# Sheet2.net
KiCad netlist of a schematic drawn in Altium Designer
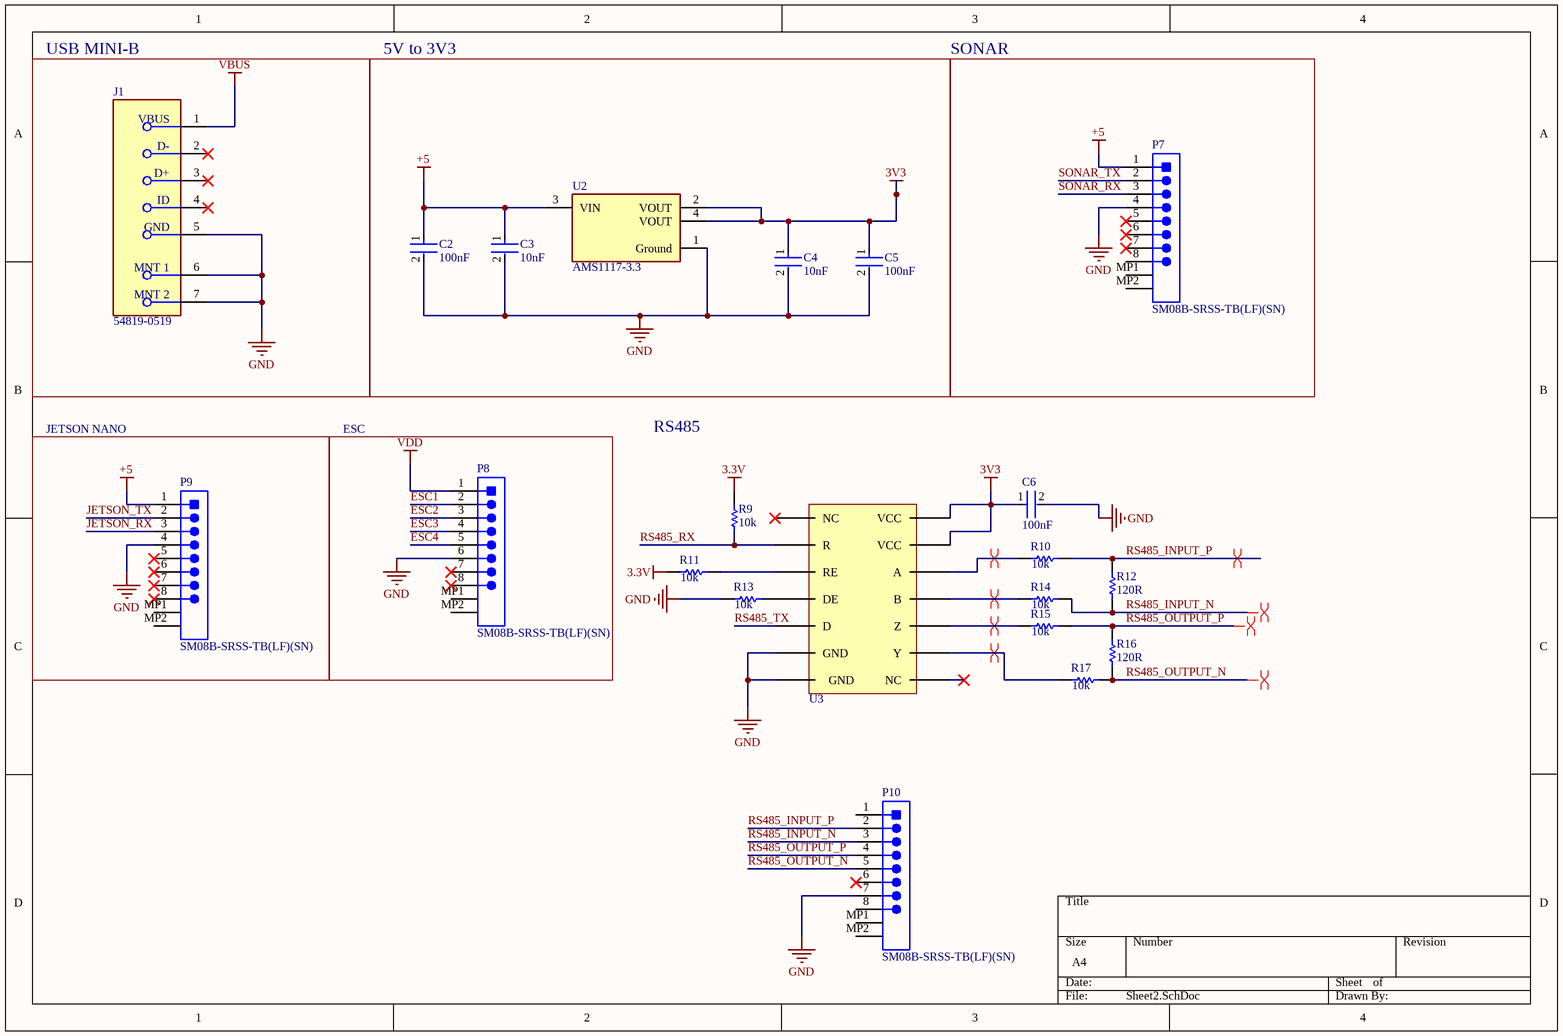
[diagram p0: Sheet2.SchDoc]

(export (version "E")
  (design (tool "Eeschema 10.0.6"))
  (components
    (comp (ref "C2")
      (value "100nF")
      (footprint "FP-C0402-BB-MFG")
      (description "CAP CER 0.1UF 10V X5R 0402")
      (fields (field (name "MANUFACTURER") "Kemet") (field (name "TOLERANCE") "0.1"))
      (libsource (lib "Altium Content Vault") (part "b4654b650e69147ec39a6b967a45e02"))
    )
    (comp (ref "C3")
      (value "10nF")
      (footprint "FP-C0402-BB-MFG")
      (description "CAP CER 0.1UF 10V X5R 0402")
      (fields (field (name "MANUFACTURER") "Kemet") (field (name "TOLERANCE") "0.1"))
      (libsource (lib "Altium Content Vault") (part "b4654b650e69147ec39a6b967a45e02"))
    )
    (comp (ref "C4")
      (value "10nF")
      (footprint "FP-C0402-BB-MFG")
      (description "CAP CER 0.1UF 10V X5R 0402")
      (fields (field (name "MANUFACTURER") "Kemet") (field (name "TOLERANCE") "0.1"))
      (libsource (lib "Altium Content Vault") (part "b4654b650e69147ec39a6b967a45e02"))
    )
    (comp (ref "C5")
      (value "100nF")
      (footprint "FP-C0402-BB-MFG")
      (description "CAP CER 0.1UF 10V X5R 0402")
      (fields (field (name "MANUFACTURER") "Kemet") (field (name "TOLERANCE") "0.1"))
      (libsource (lib "Altium Content Vault") (part "b4654b650e69147ec39a6b967a45e02"))
    )
    (comp (ref "C6")
      (value "100nF")
      (footprint "FP-C0402-BB-MFG")
      (description "CAP CER 0.1UF 10V X5R 0402")
      (fields (field (name "MANUFACTURER") "Kemet") (field (name "TOLERANCE") "0.1"))
      (libsource (lib "Altium Content Vault") (part "b4654b650e69147ec39a6b967a45e02"))
    )
    (comp (ref "J1")
      (value "54819-0519")
      (footprint "FP-54819-0519-MFG")
      (description "CONN RCPT USB2.0 MINI B 5P R/A")
      (libsource (lib "Altium Content Vault") (part "0bee2869d159fa7a73e2a5ef735a9a6"))
    )
    (comp (ref "P7")
      (value "SM08B-SRSS-TB(LF)(SN)")
      (footprint "JST-SM08B-SRSS-TB_V")
      (description "Male Header, Pitch 1 mm, 1 x 8 Position, Height 2.95 mm, -25 to 85 degC, RoHS, Tape and Reel")
      (fields (field (name "MANUFACTURER") "JST"))
      (libsource (lib "Altium Content Vault") (part "CN-1P-2M-R8"))
    )
    (comp (ref "P8")
      (value "SM08B-SRSS-TB(LF)(SN)")
      (footprint "JST-SM08B-SRSS-TB_V")
      (description "Male Header, Pitch 1 mm, 1 x 8 Position, Height 2.95 mm, -25 to 85 degC, RoHS, Tape and Reel")
      (fields (field (name "MANUFACTURER") "JST"))
      (libsource (lib "Altium Content Vault") (part "CN-1P-2M-R8"))
    )
    (comp (ref "P9")
      (value "SM08B-SRSS-TB(LF)(SN)")
      (footprint "JST-SM08B-SRSS-TB_V")
      (description "Male Header, Pitch 1 mm, 1 x 8 Position, Height 2.95 mm, -25 to 85 degC, RoHS, Tape and Reel")
      (fields (field (name "MANUFACTURER") "JST"))
      (libsource (lib "Altium Content Vault") (part "CN-1P-2M-R8"))
    )
    (comp (ref "P10")
      (value "SM08B-SRSS-TB(LF)(SN)")
      (footprint "JST-SM08B-SRSS-TB_V")
      (description "Male Header, Pitch 1 mm, 1 x 8 Position, Height 2.95 mm, -25 to 85 degC, RoHS, Tape and Reel")
      (fields (field (name "MANUFACTURER") "JST"))
      (libsource (lib "Altium Content Vault") (part "CN-1P-2M-R8"))
    )
    (comp (ref "R9")
      (value "10k")
      (footprint "RESC1609X50X30LL8T20")
      (description "Chip Resistor, 10 KOhm, +/- 1%, 100 mW, -55 to 155 degC, 0603 (1608 Metric), RoHS, Tape and Reel")
      (fields (field (name "MANUFACTURER") "Vishay Semiconductor"))
      (libsource (lib "Altium Content Vault") (part "RES-2"))
    )
    (comp (ref "R10")
      (value "10k")
      (footprint "RESC1609X50X30LL8T20")
      (description "Chip Resistor, 10 KOhm, +/- 1%, 100 mW, -55 to 155 degC, 0603 (1608 Metric), RoHS, Tape and Reel")
      (fields (field (name "MANUFACTURER") "Vishay Semiconductor"))
      (libsource (lib "Altium Content Vault") (part "RES-2"))
    )
    (comp (ref "R11")
      (value "10k")
      (footprint "RESC1609X50X30LL8T20")
      (description "Chip Resistor, 10 KOhm, +/- 1%, 100 mW, -55 to 155 degC, 0603 (1608 Metric), RoHS, Tape and Reel")
      (fields (field (name "MANUFACTURER") "Vishay Semiconductor"))
      (libsource (lib "Altium Content Vault") (part "RES-2"))
    )
    (comp (ref "R12")
      (value "120R")
      (footprint "RESC1609X50X30LL8T20")
      (description "Chip Resistor, 10 KOhm, +/- 1%, 100 mW, -55 to 155 degC, 0603 (1608 Metric), RoHS, Tape and Reel")
      (fields (field (name "MANUFACTURER") "Vishay Semiconductor"))
      (libsource (lib "Altium Content Vault") (part "RES-2"))
    )
    (comp (ref "R13")
      (value "10k")
      (footprint "RESC1609X50X30LL8T20")
      (description "Chip Resistor, 10 KOhm, +/- 1%, 100 mW, -55 to 155 degC, 0603 (1608 Metric), RoHS, Tape and Reel")
      (fields (field (name "MANUFACTURER") "Vishay Semiconductor"))
      (libsource (lib "Altium Content Vault") (part "RES-2"))
    )
    (comp (ref "R14")
      (value "10k")
      (footprint "RESC1609X50X30LL8T20")
      (description "Chip Resistor, 10 KOhm, +/- 1%, 100 mW, -55 to 155 degC, 0603 (1608 Metric), RoHS, Tape and Reel")
      (fields (field (name "MANUFACTURER") "Vishay Semiconductor"))
      (libsource (lib "Altium Content Vault") (part "RES-2"))
    )
    (comp (ref "R15")
      (value "10k")
      (footprint "RESC1609X50X30LL8T20")
      (description "Chip Resistor, 10 KOhm, +/- 1%, 100 mW, -55 to 155 degC, 0603 (1608 Metric), RoHS, Tape and Reel")
      (fields (field (name "MANUFACTURER") "Vishay Semiconductor"))
      (libsource (lib "Altium Content Vault") (part "RES-2"))
    )
    (comp (ref "R16")
      (value "120R")
      (footprint "RESC1609X50X30LL8T20")
      (description "Chip Resistor, 10 KOhm, +/- 1%, 100 mW, -55 to 155 degC, 0603 (1608 Metric), RoHS, Tape and Reel")
      (fields (field (name "MANUFACTURER") "Vishay Semiconductor"))
      (libsource (lib "Altium Content Vault") (part "RES-2"))
    )
    (comp (ref "R17")
      (value "10k")
      (footprint "RESC1609X50X30LL8T20")
      (description "Chip Resistor, 10 KOhm, +/- 1%, 100 mW, -55 to 155 degC, 0603 (1608 Metric), RoHS, Tape and Reel")
      (fields (field (name "MANUFACTURER") "Vishay Semiconductor"))
      (libsource (lib "Altium Content Vault") (part "RES-2"))
    )
    (comp (ref "U2")
      (value "AMS1117-3.3")
      (footprint "FP-AMS1117-IPC_C")
      (description "LDO Voltage Regulators 1A, 3.3V")
      (fields
        (field (name "OCTOPART") "https://octopart.com/ams1117-3.3-advanced+monolithic+systems-25899300")
        (field (name "MANUFACTURER") "Advanced Monolithic Systems")
      )
      (libsource (lib "Altium Content Vault") (part "8bdbb5f8e77002000e30dd2845d0354"))
    )
    (comp (ref "U3")
      (value "SN65HVD1473D")
      (footprint "SOIC127P600X175-14N:SOIC127P600X175-14N")
      (libsource (lib "SN65HVD1473D") (part "SN65HVD1473D"))
    )
  )
  (nets
    (net (code "1") (name "+5") (class "Default")
      (node (ref "C2") (pin "1") (pinfunction "1_1") (pintype "passive"))
      (node (ref "C3") (pin "1") (pinfunction "1_1") (pintype "passive"))
      (node (ref "P7") (pin "1") (pinfunction "1_1") (pintype "passive"))
      (node (ref "P9") (pin "1") (pinfunction "1_1") (pintype "passive"))
      (node (ref "U2") (pin "3") (pinfunction "VIN_3") (pintype "power_in"))
    )
    (net (code "2") (name "/ESC1") (class "Default")
      (node (ref "P8") (pin "2") (pinfunction "2_2") (pintype "passive"))
    )
    (net (code "3") (name "/ESC2") (class "Default")
      (node (ref "P8") (pin "3") (pinfunction "3_3") (pintype "passive"))
    )
    (net (code "4") (name "/ESC3") (class "Default")
      (node (ref "P8") (pin "4") (pinfunction "4_4") (pintype "passive"))
    )
    (net (code "5") (name "/ESC4") (class "Default")
      (node (ref "P8") (pin "5") (pinfunction "5_5") (pintype "passive"))
    )
    (net (code "6") (name "/JETSON_RX") (class "Default")
      (node (ref "P9") (pin "3") (pinfunction "3_3") (pintype "passive"))
    )
    (net (code "7") (name "/JETSON_TX") (class "Default")
      (node (ref "P9") (pin "2") (pinfunction "2_2") (pintype "passive"))
    )
    (net (code "8") (name "/RS485_INPUT_N") (class "Default")
      (node (ref "P10") (pin "3") (pinfunction "3_3") (pintype "passive"))
      (node (ref "R12") (pin "1") (pinfunction "1_1") (pintype "passive"))
      (node (ref "R14") (pin "2") (pinfunction "2_2") (pintype "passive"))
    )
    (net (code "9") (name "/RS485_INPUT_P") (class "Default")
      (node (ref "P10") (pin "2") (pinfunction "2_2") (pintype "passive"))
      (node (ref "R10") (pin "2") (pinfunction "2_2") (pintype "passive"))
      (node (ref "R12") (pin "2") (pinfunction "2_2") (pintype "passive"))
    )
    (net (code "10") (name "/RS485_OUTPUT_N") (class "Default")
      (node (ref "P10") (pin "5") (pinfunction "5_5") (pintype "passive"))
      (node (ref "R16") (pin "1") (pinfunction "1_1") (pintype "passive"))
      (node (ref "R17") (pin "2") (pinfunction "2_2") (pintype "passive"))
    )
    (net (code "11") (name "/RS485_OUTPUT_P") (class "Default")
      (node (ref "P10") (pin "4") (pinfunction "4_4") (pintype "passive"))
      (node (ref "R15") (pin "2") (pinfunction "2_2") (pintype "passive"))
      (node (ref "R16") (pin "2") (pinfunction "2_2") (pintype "passive"))
    )
    (net (code "12") (name "/RS485_RX") (class "Default")
      (node (ref "R9") (pin "1") (pinfunction "1_1") (pintype "passive"))
      (node (ref "U3") (pin "R") (pinfunction "R_R") (pintype "passive"))
    )
    (net (code "13") (name "/RS485_TX") (class "Default")
      (node (ref "U3") (pin "13") (pinfunction "D_13") (pintype "passive"))
    )
    (net (code "14") (name "/SONAR_RX") (class "Default")
      (node (ref "P7") (pin "3") (pinfunction "3_3") (pintype "passive"))
    )
    (net (code "15") (name "/SONAR_TX") (class "Default")
      (node (ref "P7") (pin "2") (pinfunction "2_2") (pintype "passive"))
    )
    (net (code "16") (name "3.3V") (class "Default")
      (node (ref "R11") (pin "1") (pinfunction "1_1") (pintype "passive"))
      (node (ref "R9") (pin "2") (pinfunction "2_2") (pintype "passive"))
    )
    (net (code "17") (name "3V3") (class "Default")
      (node (ref "C4") (pin "1") (pinfunction "1_1") (pintype "passive"))
      (node (ref "C5") (pin "1") (pinfunction "1_1") (pintype "passive"))
      (node (ref "C6") (pin "1") (pinfunction "1_1") (pintype "passive"))
      (node (ref "U2") (pin "2") (pinfunction "VOUT_2") (pintype "passive"))
      (node (ref "U2") (pin "4") (pinfunction "VOUT_4") (pintype "passive"))
      (node (ref "U3") (pin "16") (pinfunction "VCC_16") (pintype "passive"))
      (node (ref "U3") (pin "22") (pinfunction "VCC_22") (pintype "passive"))
    )
    (net (code "18") (name "GND") (class "Default")
      (node (ref "C2") (pin "2") (pinfunction "2_2") (pintype "passive"))
      (node (ref "C3") (pin "2") (pinfunction "2_2") (pintype "passive"))
      (node (ref "C4") (pin "2") (pinfunction "2_2") (pintype "passive"))
      (node (ref "C5") (pin "2") (pinfunction "2_2") (pintype "passive"))
      (node (ref "C6") (pin "2") (pinfunction "2_2") (pintype "passive"))
      (node (ref "J1") (pin "5") (pinfunction "GND_5") (pintype "power_in"))
      (node (ref "J1") (pin "6") (pinfunction "MNT_1_6") (pintype "passive"))
      (node (ref "J1") (pin "7") (pinfunction "MNT_2_7") (pintype "passive"))
      (node (ref "P10") (pin "7") (pinfunction "7_7") (pintype "passive"))
      (node (ref "P7") (pin "4") (pinfunction "4_4") (pintype "passive"))
      (node (ref "P8") (pin "6") (pinfunction "6_6") (pintype "passive"))
      (node (ref "P9") (pin "4") (pinfunction "4_4") (pintype "passive"))
      (node (ref "R13") (pin "1") (pinfunction "1_1") (pintype "passive"))
      (node (ref "U2") (pin "1") (pinfunction "Ground_1") (pintype "power_in"))
      (node (ref "U3") (pin "11") (pinfunction "__GND_11") (pintype "passive"))
      (node (ref "U3") (pin "12") (pinfunction "GND_12") (pintype "passive"))
    )
    (net (code "19") (name "Net-(U3-A)") (class "Default")
      (node (ref "R10") (pin "1") (pinfunction "1_1") (pintype "passive"))
      (node (ref "U3") (pin "21") (pinfunction "A_21") (pintype "passive"))
    )
    (net (code "20") (name "Net-(U3-B)") (class "Default")
      (node (ref "R14") (pin "1") (pinfunction "1_1") (pintype "passive"))
      (node (ref "U3") (pin "20") (pinfunction "B_20") (pintype "passive"))
    )
    (net (code "21") (name "Net-(U3-DE)") (class "Default")
      (node (ref "R13") (pin "2") (pinfunction "2_2") (pintype "passive"))
      (node (ref "U3") (pin "14") (pinfunction "DE_14") (pintype "passive"))
    )
    (net (code "22") (name "Net-(U3-RE)") (class "Default")
      (node (ref "R11") (pin "2") (pinfunction "2_2") (pintype "passive"))
      (node (ref "U3") (pin "15") (pinfunction "RE_15") (pintype "passive"))
    )
    (net (code "23") (name "Net-(U3-Y)") (class "Default")
      (node (ref "R17") (pin "1") (pinfunction "1_1") (pintype "passive"))
      (node (ref "U3") (pin "18") (pinfunction "Y_18") (pintype "passive"))
    )
    (net (code "24") (name "Net-(U3-Z)") (class "Default")
      (node (ref "R15") (pin "1") (pinfunction "1_1") (pintype "passive"))
      (node (ref "U3") (pin "19") (pinfunction "Z_19") (pintype "passive"))
    )
    (net (code "25") (name "VBUS") (class "Default")
      (node (ref "J1") (pin "1") (pinfunction "VBUS_1") (pintype "power_in"))
    )
    (net (code "26") (name "VDD") (class "Default")
      (node (ref "P8") (pin "1") (pinfunction "1_1") (pintype "passive"))
    )
    (net (code "27") (name "unconnected-(J1-D+-Pad3)") (class "Default")
      (node (ref "J1") (pin "3") (pinfunction "D+_3") (pintype "passive+no_connect"))
    )
    (net (code "28") (name "unconnected-(J1-D--Pad2)") (class "Default")
      (node (ref "J1") (pin "2") (pinfunction "D-_2") (pintype "passive+no_connect"))
    )
    (net (code "29") (name "unconnected-(J1-ID-Pad4)") (class "Default")
      (node (ref "J1") (pin "4") (pinfunction "ID_4") (pintype "passive+no_connect"))
    )
    (net (code "30") (name "unconnected-(P7-Pad5)") (class "Default")
      (node (ref "P7") (pin "5") (pinfunction "5_5") (pintype "passive+no_connect"))
    )
    (net (code "31") (name "unconnected-(P7-Pad6)") (class "Default")
      (node (ref "P7") (pin "6") (pinfunction "6_6") (pintype "passive+no_connect"))
    )
    (net (code "32") (name "unconnected-(P7-Pad7)") (class "Default")
      (node (ref "P7") (pin "7") (pinfunction "7_7") (pintype "passive+no_connect"))
    )
    (net (code "33") (name "unconnected-(P7-Pad8)") (class "Default")
      (node (ref "P7") (pin "8") (pinfunction "8_8") (pintype "passive"))
    )
    (net (code "34") (name "unconnected-(P7-PadMP1)") (class "Default")
      (node (ref "P7") (pin "MP1") (pinfunction "MP1_MP1") (pintype "passive"))
    )
    (net (code "35") (name "unconnected-(P7-PadMP2)") (class "Default")
      (node (ref "P7") (pin "MP2") (pinfunction "MP2_MP2") (pintype "passive"))
    )
    (net (code "36") (name "unconnected-(P8-Pad7)") (class "Default")
      (node (ref "P8") (pin "7") (pinfunction "7_7") (pintype "passive+no_connect"))
    )
    (net (code "37") (name "unconnected-(P8-Pad8)") (class "Default")
      (node (ref "P8") (pin "8") (pinfunction "8_8") (pintype "passive+no_connect"))
    )
    (net (code "38") (name "unconnected-(P8-PadMP1)") (class "Default")
      (node (ref "P8") (pin "MP1") (pinfunction "MP1_MP1") (pintype "passive"))
    )
    (net (code "39") (name "unconnected-(P8-PadMP2)") (class "Default")
      (node (ref "P8") (pin "MP2") (pinfunction "MP2_MP2") (pintype "passive"))
    )
    (net (code "40") (name "unconnected-(P9-Pad5)") (class "Default")
      (node (ref "P9") (pin "5") (pinfunction "5_5") (pintype "passive+no_connect"))
    )
    (net (code "41") (name "unconnected-(P9-Pad6)") (class "Default")
      (node (ref "P9") (pin "6") (pinfunction "6_6") (pintype "passive+no_connect"))
    )
    (net (code "42") (name "unconnected-(P9-Pad7)") (class "Default")
      (node (ref "P9") (pin "7") (pinfunction "7_7") (pintype "passive+no_connect"))
    )
    (net (code "43") (name "unconnected-(P9-Pad8)") (class "Default")
      (node (ref "P9") (pin "8") (pinfunction "8_8") (pintype "passive+no_connect"))
    )
    (net (code "44") (name "unconnected-(P9-PadMP1)") (class "Default")
      (node (ref "P9") (pin "MP1") (pinfunction "MP1_MP1") (pintype "passive"))
    )
    (net (code "45") (name "unconnected-(P9-PadMP2)") (class "Default")
      (node (ref "P9") (pin "MP2") (pinfunction "MP2_MP2") (pintype "passive"))
    )
    (net (code "46") (name "unconnected-(P10-Pad1)") (class "Default")
      (node (ref "P10") (pin "1") (pinfunction "1_1") (pintype "passive"))
    )
    (net (code "47") (name "unconnected-(P10-Pad6)") (class "Default")
      (node (ref "P10") (pin "6") (pinfunction "6_6") (pintype "passive+no_connect"))
    )
    (net (code "48") (name "unconnected-(P10-Pad8)") (class "Default")
      (node (ref "P10") (pin "8") (pinfunction "8_8") (pintype "passive"))
    )
    (net (code "49") (name "unconnected-(P10-PadMP1)") (class "Default")
      (node (ref "P10") (pin "MP1") (pinfunction "MP1_MP1") (pintype "passive"))
    )
    (net (code "50") (name "unconnected-(P10-PadMP2)") (class "Default")
      (node (ref "P10") (pin "MP2") (pinfunction "MP2_MP2") (pintype "passive"))
    )
    (net (code "51") (name "unconnected-(U3-NC-Pad9)") (class "Default")
      (node (ref "U3") (pin "9") (pinfunction "NC_9") (pintype "passive+no_connect"))
    )
    (net (code "52") (name "unconnected-(U3-NC-Pad17)") (class "Default")
      (node (ref "U3") (pin "17") (pinfunction "NC_17") (pintype "passive+no_connect"))
    )
  )
)
